# ts52002-breakout.net
KiCad netlist of a schematic drawn in EAGLE
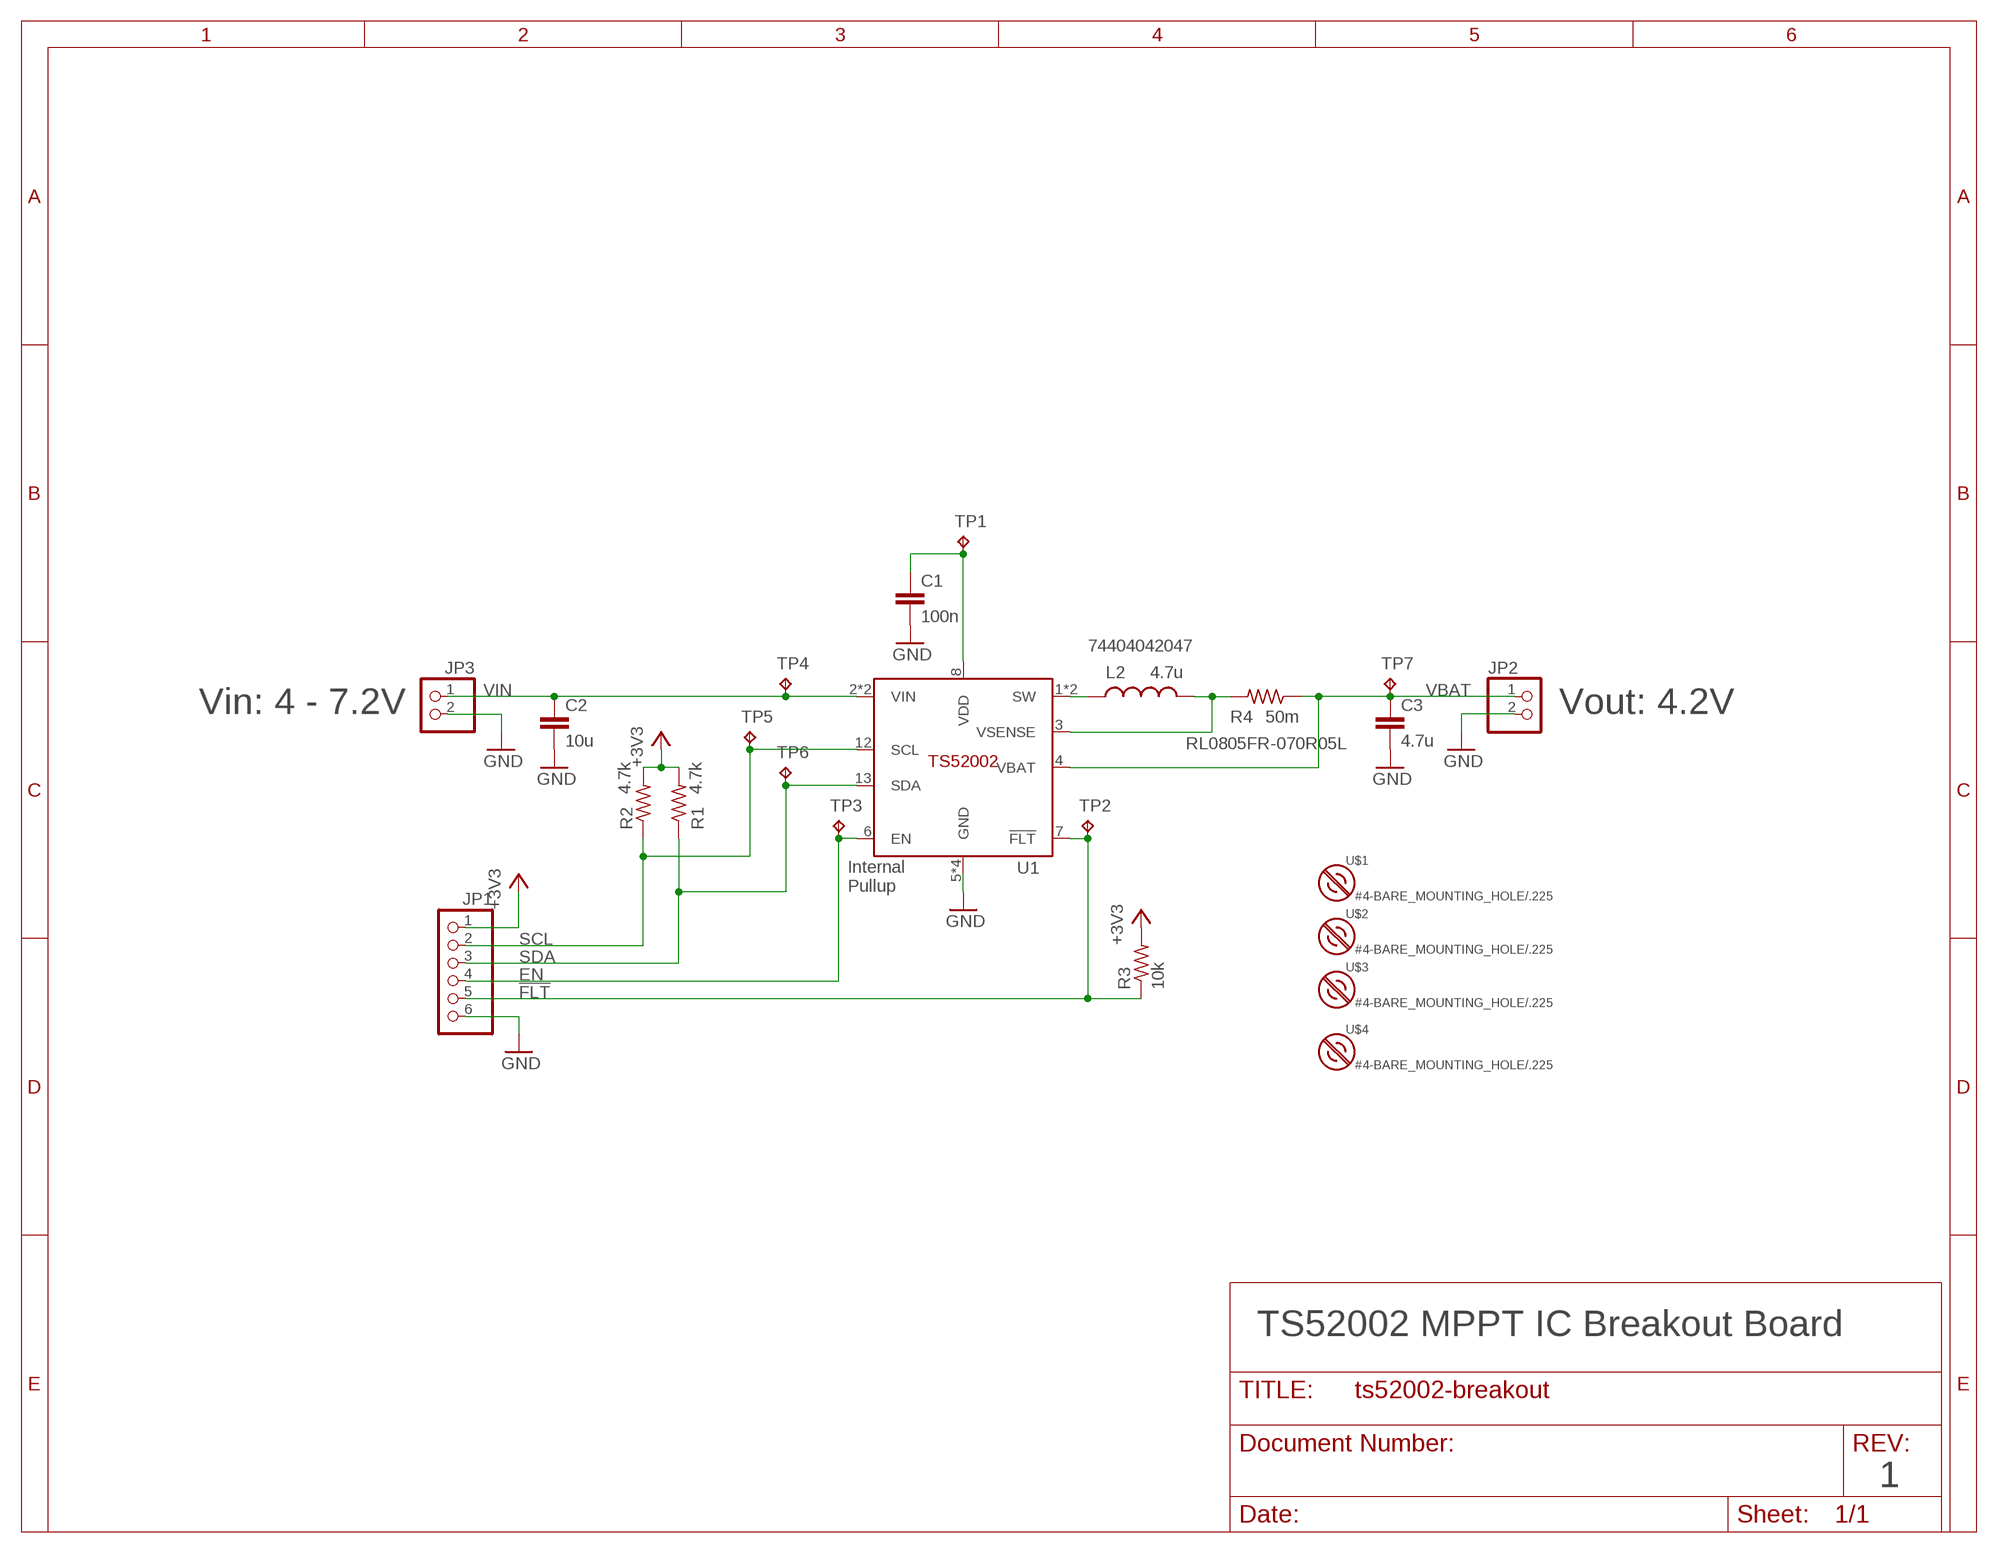
[diagram p0: schematic, sheet 1]

(export (version "E")
  (design (tool "Eeschema 10.0.6"))
  (components
    (comp (ref "C1")
      (value "100n")
      (footprint "eagle-import:.0603-B-NOSILK")
      (libsource (lib "eagle-import") (part "C-EU0603-B-NOSILK"))
    )
    (comp (ref "C2")
      (value "10u")
      (footprint "eagle-import:.0805-B-NOSILK")
      (libsource (lib "eagle-import") (part "C-EU0805-B-NOSILK"))
    )
    (comp (ref "C3")
      (value "4.7u")
      (footprint "eagle-import:.0805-B-NOSILK")
      (libsource (lib "eagle-import") (part "C-EU0805-B-NOSILK"))
    )
    (comp (ref "JP1")
      (value "PINHD-1X6")
      (footprint "eagle-import:1X06")
      (libsource (lib "eagle-import") (part "PINHD-1X6"))
    )
    (comp (ref "JP2")
      (value "PINHD-1X2")
      (footprint "eagle-import:1X02")
      (libsource (lib "eagle-import") (part "PINHD-1X2"))
    )
    (comp (ref "JP3")
      (value "PINHD-1X2")
      (footprint "eagle-import:1X02")
      (libsource (lib "eagle-import") (part "PINHD-1X2"))
    )
    (comp (ref "L2")
      (value "4.7u")
      (footprint "eagle-import:WURTH-4518")
      (libsource (lib "eagle-import") (part "WURTH-4518-INDUCTOR"))
    )
    (comp (ref "R1")
      (value "4.7k")
      (footprint "eagle-import:.0603-B-NOSILK")
      (libsource (lib "eagle-import") (part "R-US_0603-B-NOSILK"))
    )
    (comp (ref "R2")
      (value "4.7k")
      (footprint "eagle-import:.0603-B-NOSILK")
      (libsource (lib "eagle-import") (part "R-US_0603-B-NOSILK"))
    )
    (comp (ref "R3")
      (value "10k")
      (footprint "eagle-import:.0603-B-NOSILK")
      (libsource (lib "eagle-import") (part "R-US_0603-B-NOSILK"))
    )
    (comp (ref "R4")
      (value "50m")
      (footprint "eagle-import:.0805-B-NOSILK")
      (libsource (lib "eagle-import") (part "R-US_0805-B-NOSILK"))
    )
    (comp (ref "TP1")
      (value "TPPAD1-13")
      (footprint "eagle-import:P1-13")
      (libsource (lib "eagle-import") (part "TPPAD1-13"))
    )
    (comp (ref "TP2")
      (value "TPPAD1-13")
      (footprint "eagle-import:P1-13")
      (libsource (lib "eagle-import") (part "TPPAD1-13"))
    )
    (comp (ref "TP3")
      (value "TPPAD1-13")
      (footprint "eagle-import:P1-13")
      (libsource (lib "eagle-import") (part "TPPAD1-13"))
    )
    (comp (ref "TP4")
      (value "TPPAD1-13")
      (footprint "eagle-import:P1-13")
      (libsource (lib "eagle-import") (part "TPPAD1-13"))
    )
    (comp (ref "TP5")
      (value "TPPAD1-13")
      (footprint "eagle-import:P1-13")
      (libsource (lib "eagle-import") (part "TPPAD1-13"))
    )
    (comp (ref "TP6")
      (value "TPPAD1-13")
      (footprint "eagle-import:P1-13")
      (libsource (lib "eagle-import") (part "TPPAD1-13"))
    )
    (comp (ref "TP7")
      (value "TPPAD1-13")
      (footprint "eagle-import:P1-13")
      (libsource (lib "eagle-import") (part "TPPAD1-13"))
    )
    (comp (ref "U$1")
      (value "#4-BARE_MOUNTING_HOLE/.225")
      (footprint "eagle-import:#4_.225-BARE+HEAD_OR_SMALL_NUT")
      (libsource (lib "eagle-import") (part "#4-BARE_MOUNTING_HOLE/.225"))
    )
    (comp (ref "U$2")
      (value "#4-BARE_MOUNTING_HOLE/.225")
      (footprint "eagle-import:#4_.225-BARE+HEAD_OR_SMALL_NUT")
      (libsource (lib "eagle-import") (part "#4-BARE_MOUNTING_HOLE/.225"))
    )
    (comp (ref "U$3")
      (value "#4-BARE_MOUNTING_HOLE/.225")
      (footprint "eagle-import:#4_.225-BARE+HEAD_OR_SMALL_NUT")
      (libsource (lib "eagle-import") (part "#4-BARE_MOUNTING_HOLE/.225"))
    )
    (comp (ref "U$4")
      (value "#4-BARE_MOUNTING_HOLE/.225")
      (footprint "eagle-import:#4_.225-BARE+HEAD_OR_SMALL_NUT")
      (libsource (lib "eagle-import") (part "#4-BARE_MOUNTING_HOLE/.225"))
    )
    (comp (ref "U1")
      (value "TS52002")
      (footprint "eagle-import:QFN-32-WITH-CENTER-PAD")
      (libsource (lib "eagle-import") (part "TS52002"))
    )
  )
  (nets
    (net (code "1") (name "+3V3") (class "Default")
      (node (ref "JP1") (pin "1") (pinfunction "1_1") (pintype "passive"))
      (node (ref "R1") (pin "2") (pinfunction "2_2") (pintype "passive"))
      (node (ref "R2") (pin "2") (pinfunction "2_2") (pintype "passive"))
      (node (ref "R3") (pin "2") (pinfunction "2_2") (pintype "passive"))
    )
    (net (code "2") (name "/EN") (class "Default")
      (node (ref "JP1") (pin "4") (pinfunction "4_4") (pintype "passive"))
      (node (ref "TP3") (pin "TP") (pinfunction "TP_TP") (pintype "input"))
      (node (ref "U1") (pin "6") (pinfunction "EN_6") (pintype "input"))
    )
    (net (code "3") (name "/SCL") (class "Default")
      (node (ref "JP1") (pin "2") (pinfunction "2_2") (pintype "passive"))
      (node (ref "R2") (pin "1") (pinfunction "1_1") (pintype "passive"))
      (node (ref "TP5") (pin "TP") (pinfunction "TP_TP") (pintype "input"))
      (node (ref "U1") (pin "12") (pinfunction "SCL_12") (pintype "input"))
    )
    (net (code "4") (name "/SDA") (class "Default")
      (node (ref "JP1") (pin "3") (pinfunction "3_3") (pintype "passive"))
      (node (ref "R1") (pin "1") (pinfunction "1_1") (pintype "passive"))
      (node (ref "TP6") (pin "TP") (pinfunction "TP_TP") (pintype "input"))
      (node (ref "U1") (pin "13") (pinfunction "SDA_13") (pintype "bidirectional"))
    )
    (net (code "5") (name "/VBAT") (class "Default")
      (node (ref "C3") (pin "1") (pinfunction "1_1") (pintype "passive"))
      (node (ref "JP2") (pin "1") (pinfunction "1_1") (pintype "passive"))
      (node (ref "R4") (pin "1") (pinfunction "1_1") (pintype "passive"))
      (node (ref "TP7") (pin "TP") (pinfunction "TP_TP") (pintype "input"))
      (node (ref "U1") (pin "4") (pinfunction "VBAT_4") (pintype "power_in"))
    )
    (net (code "6") (name "/VIN") (class "Default")
      (node (ref "C2") (pin "1") (pinfunction "1_1") (pintype "passive"))
      (node (ref "JP3") (pin "1") (pinfunction "1_1") (pintype "passive"))
      (node (ref "TP4") (pin "TP") (pinfunction "TP_TP") (pintype "input"))
      (node (ref "U1") (pin "11") (pinfunction "VIN_11") (pintype "power_in"))
      (node (ref "U1") (pin "2") (pinfunction "VIN_2") (pintype "power_in"))
    )
    (net (code "7") (name "/~{FLT}") (class "Default")
      (node (ref "JP1") (pin "5") (pinfunction "5_5") (pintype "passive"))
      (node (ref "R3") (pin "1") (pinfunction "1_1") (pintype "passive"))
      (node (ref "TP2") (pin "TP") (pinfunction "TP_TP") (pintype "input"))
      (node (ref "U1") (pin "7") (pinfunction "~{FLT}_7") (pintype "open_collector"))
    )
    (net (code "8") (name "GND") (class "Default")
      (node (ref "C1") (pin "2") (pinfunction "2_2") (pintype "passive"))
      (node (ref "C2") (pin "2") (pinfunction "2_2") (pintype "passive"))
      (node (ref "C3") (pin "2") (pinfunction "2_2") (pintype "passive"))
      (node (ref "JP1") (pin "6") (pinfunction "6_6") (pintype "passive"))
      (node (ref "JP2") (pin "2") (pinfunction "2_2") (pintype "passive"))
      (node (ref "JP3") (pin "2") (pinfunction "2_2") (pintype "passive"))
      (node (ref "U1") (pin "15") (pinfunction "GND_15") (pintype "power_in"))
      (node (ref "U1") (pin "16") (pinfunction "GND_16") (pintype "power_in"))
      (node (ref "U1") (pin "5") (pinfunction "GND_5") (pintype "power_in"))
      (node (ref "U1") (pin "PAD") (pinfunction "GND_PAD") (pintype "power_in"))
    )
    (net (code "9") (name "Net-(L2-1)") (class "Default")
      (node (ref "L2") (pin "P$1") (pinfunction "1_P$1") (pintype "passive"))
      (node (ref "U1") (pin "1") (pinfunction "SW_1") (pintype "bidirectional"))
      (node (ref "U1") (pin "14") (pinfunction "SW_14") (pintype "bidirectional"))
    )
    (net (code "10") (name "Net-(L2-2)") (class "Default")
      (node (ref "L2") (pin "P$2") (pinfunction "2_P$2") (pintype "passive"))
      (node (ref "R4") (pin "2") (pinfunction "2_2") (pintype "passive"))
      (node (ref "U1") (pin "3") (pinfunction "VSENSE_3") (pintype "bidirectional"))
    )
    (net (code "11") (name "Net-(U1-VDD)") (class "Default")
      (node (ref "C1") (pin "1") (pinfunction "1_1") (pintype "passive"))
      (node (ref "TP1") (pin "TP") (pinfunction "TP_TP") (pintype "input"))
      (node (ref "U1") (pin "8") (pinfunction "VDD_8") (pintype "power_in"))
    )
  )
)
